# biv2-LRcom_1a.net
KiCad netlist of a schematic drawn in Altium Designer
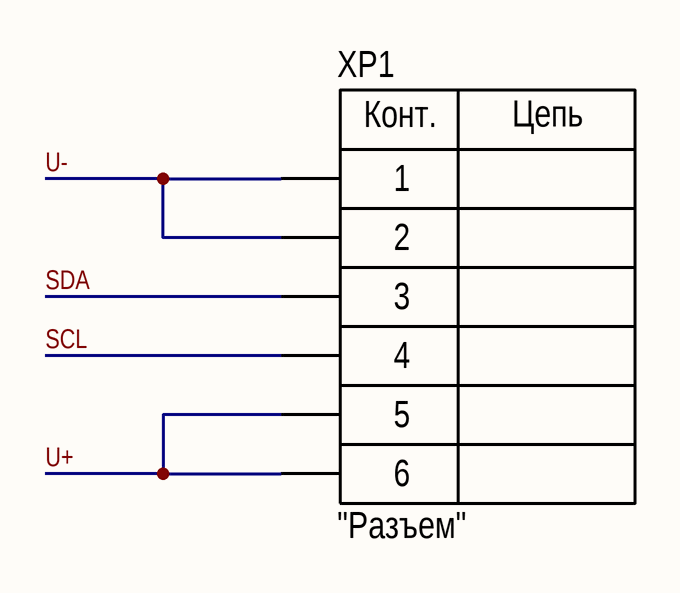
[diagram p0: biv2-LRcom_1a.SchDoc]

(export (version "E")
  (design (tool "Eeschema 10.0.6"))
  (components
    (comp (ref "XP1")
      (value "~")
      (footprint "CON: IDC-6MS")
      (fields
        (field (name "MANUFACTURER") "Connfly")
        (field (name "VALUEMANUFACTURERPARTNUMBER") "Connector, 6pin, 2.54mm, 250VAC, 3A")
        (field (name "PARTNUMBER") "IDC-6")
        (field (name "COMMENTTEXT") "\"Разъем\"")
      )
      (libsource (lib "connector") (part "IDC-6"))
    )
  )
  (nets
    (net (code "1") (name "/SCL") (class "Default")
      (node (ref "XP1") (pin "4") (pinfunction "4_4") (pintype "power_in"))
    )
    (net (code "2") (name "/SDA") (class "Default")
      (node (ref "XP1") (pin "3") (pinfunction "3_3") (pintype "power_in"))
    )
    (net (code "3") (name "/U+") (class "Default")
      (node (ref "XP1") (pin "5") (pinfunction "5_5") (pintype "power_in"))
      (node (ref "XP1") (pin "6") (pinfunction "6_6") (pintype "power_in"))
    )
    (net (code "4") (name "/U-") (class "Default")
      (node (ref "XP1") (pin "1") (pinfunction "1_1") (pintype "passive"))
      (node (ref "XP1") (pin "2") (pinfunction "2_2") (pintype "passive"))
    )
  )
)
